# nRF52832_extend.net
KiCad netlist of a schematic drawn in Altium Designer
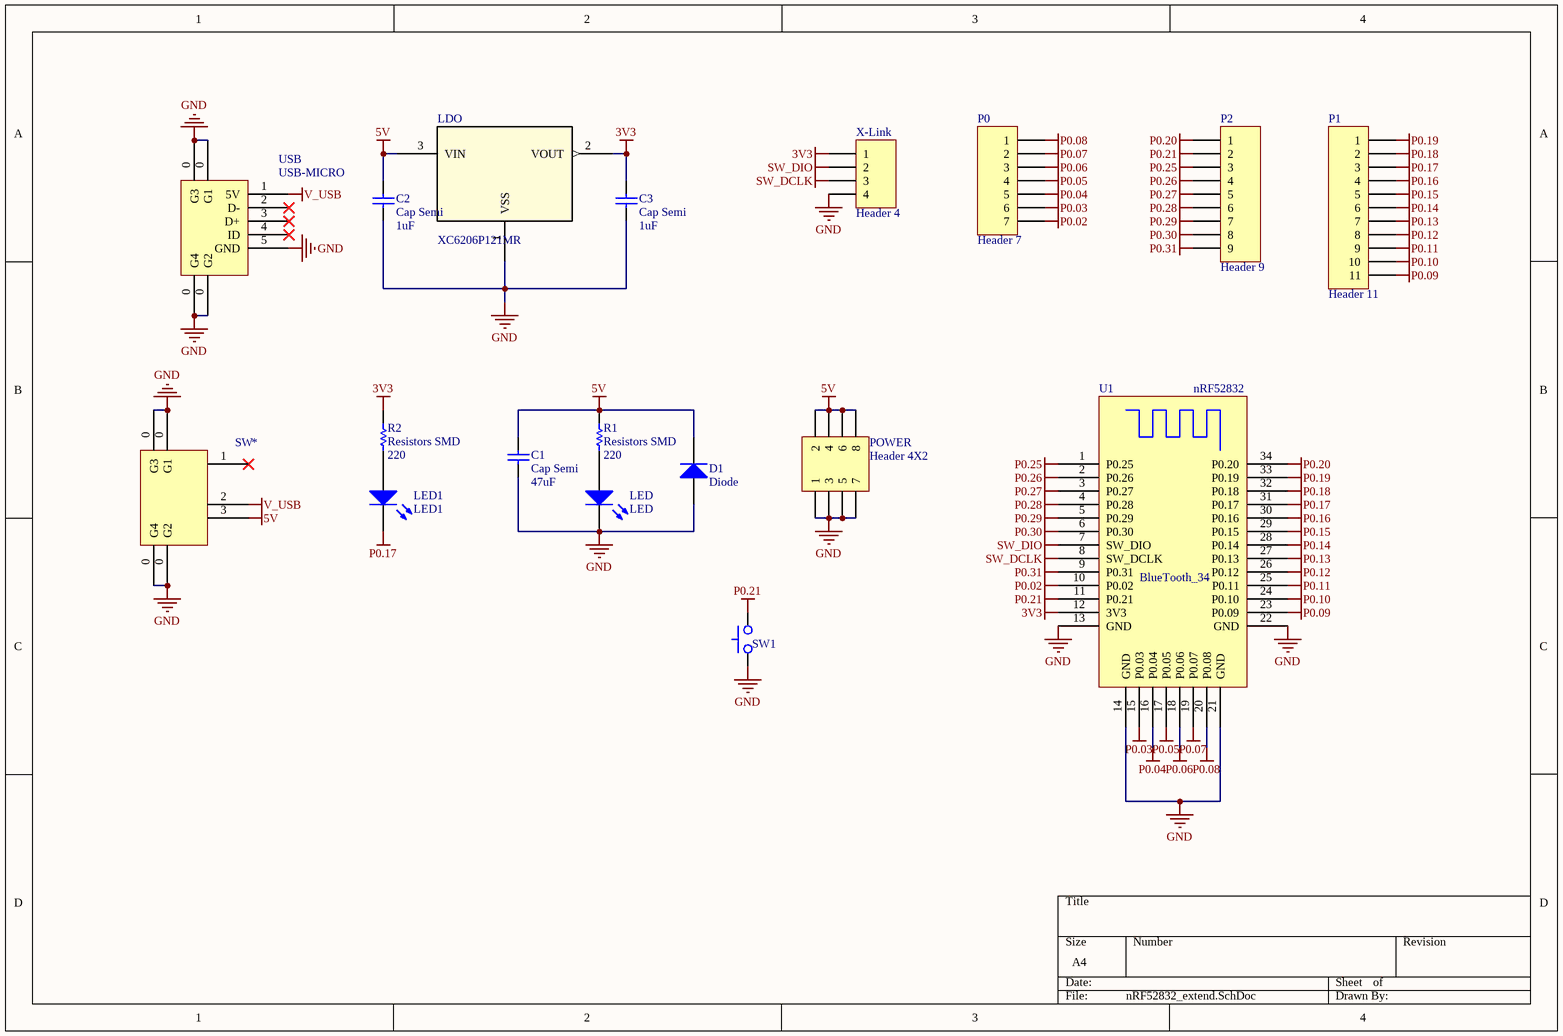
[diagram p0: nRF52832_extend.SchDoc]

(export (version "E")
  (design (tool "Eeschema 10.0.6"))
  (components
    (comp (ref "*") (value "SW") (footprint "SW_mk12c02") (libsource (lib "Mylibrary") (part "SW_mk12c02")))
    (comp (ref "C1")
      (value "Cap Semi")
      (footprint "C0805")
      (description "Capacitor (Semiconductor SIM Model)")
      (fields (field (name "ALTIUM_VALUE") "47uF") (field (name "PUBLISHER") "Altium Limited"))
      (libsource (lib "Mylibrary") (part "Cap Semi"))
    )
    (comp (ref "C2")
      (value "Cap Semi")
      (footprint "C0805")
      (description "Capacitor (Semiconductor SIM Model)")
      (fields (field (name "ALTIUM_VALUE") "1uF") (field (name "PUBLISHER") "Altium Limited"))
      (libsource (lib "Mylibrary") (part "Cap Semi"))
    )
    (comp (ref "C3")
      (value "Cap Semi")
      (footprint "C0805")
      (description "Capacitor (Semiconductor SIM Model)")
      (fields (field (name "ALTIUM_VALUE") "1uF") (field (name "PUBLISHER") "Altium Limited"))
      (libsource (lib "Mylibrary") (part "Cap Semi"))
    )
    (comp (ref "D1")
      (value "Diode")
      (footprint "6-0805_M")
      (description "Default Diode")
      (fields (field (name "PUBLISHER") "Altium Limited"))
      (libsource (lib "Miscellaneous Devices") (part "Diode"))
    )
    (comp (ref "LDO")
      (value "XC6206P121MR")
      (footprint "SOT-23")
      (description "Imported")
      (libsource (lib "Mylibrary") (part "XC6206P121MR"))
    )
    (comp (ref "LED")
      (value "LED")
      (footprint "0805 2.0X1.25X1.1")
      (description "Typical INFRARED GaAs LED")
      (fields (field (name "PUBLISHER") "Altium Limited"))
      (libsource (lib "Mylibrary") (part "LED"))
    )
    (comp (ref "LED1")
      (value "LED1")
      (footprint "0805 2.0X1.25X1.1")
      (description "Typical INFRARED GaAs LED")
      (fields (field (name "PUBLISHER") "Altium Limited"))
      (libsource (lib "Mylibrary") (part "LED"))
    )
    (comp (ref "P0")
      (value "Header 7")
      (footprint "HDR1X7")
      (description "Header, 7-Pin")
      (fields (field (name "PUBLISHER") "Altium Limited"))
      (libsource (lib "Miscellaneous Connectors") (part "Header 7"))
    )
    (comp (ref "P1")
      (value "Header 11")
      (footprint "HDR1X11")
      (description "Header, 11-Pin")
      (fields (field (name "PUBLISHER") "Altium Limited"))
      (libsource (lib "Miscellaneous Connectors") (part "Header 11"))
    )
    (comp (ref "P2")
      (value "Header 9")
      (footprint "HDR1X9")
      (description "Header, 9-Pin")
      (fields (field (name "PUBLISHER") "Altium Limited"))
      (libsource (lib "Miscellaneous Connectors") (part "Header 9"))
    )
    (comp (ref "POWER")
      (value "Header 4X2")
      (footprint "HDR2X4")
      (description "Header, 4-Pin, Dual row")
      (fields (field (name "PUBLISHER") "Altium Limited"))
      (libsource (lib "Miscellaneous Connectors") (part "Header 4X2"))
    )
    (comp (ref "R1")
      (value "Resistors SMD")
      (footprint "6-0805_M")
      (description "Resistor")
      (fields (field (name "ALTIUM_VALUE") "220"))
      (libsource (lib "Mylibrary") (part "Resistors SMD"))
    )
    (comp (ref "R2")
      (value "Resistors SMD")
      (footprint "6-0805_M")
      (description "Resistor")
      (fields (field (name "ALTIUM_VALUE") "220"))
      (libsource (lib "Mylibrary") (part "Resistors SMD"))
    )
    (comp (ref "SW1")
      (value "SW-PB")
      (footprint "SWITCH_SMD_6x3.5")
      (description "按鈕開關")
      (fields (field (name "PUBLISHER") "Altium Limited"))
      (libsource (lib "NTUST_nRF51_TAG") (part "SW-PB"))
    )
    (comp (ref "U1")
      (value "nRF52832")
      (footprint "BlueTooth_34_SMD")
      (libsource (lib "Mylibrary") (part "nRF52832"))
    )
    (comp (ref "USB")
      (value "USB-MICRO")
      (footprint "USB-MICRO")
      (libsource (lib "Mylibrary") (part "USB-MICRO"))
    )
    (comp (ref "X-Link")
      (value "Header 4")
      (footprint "HDR1X4")
      (description "Header, 4-Pin")
      (fields (field (name "PUBLISHER") "Altium Limited"))
      (libsource (lib "Miscellaneous Connectors") (part "Header 4"))
    )
  )
  (nets
    (net (code "1") (name "3V3") (class "Default")
      (node (ref "C3") (pin "2") (pinfunction "2_2") (pintype "passive"))
      (node (ref "LDO") (pin "2") (pinfunction "VOUT_2") (pintype "output"))
      (node (ref "R2") (pin "2") (pinfunction "2_2") (pintype "passive"))
      (node (ref "U1") (pin "12") (pinfunction "3V3_12") (pintype "passive"))
      (node (ref "X-Link") (pin "1") (pinfunction "1_1") (pintype "passive"))
    )
    (net (code "2") (name "5V") (class "Default")
      (node (ref "*") (pin "3") (pintype "passive"))
      (node (ref "C1") (pin "2") (pinfunction "2_2") (pintype "passive"))
      (node (ref "C2") (pin "2") (pinfunction "2_2") (pintype "passive"))
      (node (ref "D1") (pin "2") (pinfunction "K_2") (pintype "passive"))
      (node (ref "LDO") (pin "3") (pinfunction "VIN_3") (pintype "power_in"))
      (node (ref "POWER") (pin "2") (pinfunction "2_2") (pintype "passive"))
      (node (ref "POWER") (pin "4") (pinfunction "4_4") (pintype "passive"))
      (node (ref "POWER") (pin "6") (pinfunction "6_6") (pintype "passive"))
      (node (ref "POWER") (pin "8") (pinfunction "8_8") (pintype "passive"))
      (node (ref "R1") (pin "2") (pinfunction "2_2") (pintype "passive"))
    )
    (net (code "3") (name "GND") (class "Default")
      (node (ref "*") (pin "0") (pinfunction "G2_0") (pintype "power_in"))
      (node (ref "C1") (pin "1") (pinfunction "1_1") (pintype "passive"))
      (node (ref "C2") (pin "1") (pinfunction "1_1") (pintype "passive"))
      (node (ref "C3") (pin "1") (pinfunction "1_1") (pintype "passive"))
      (node (ref "D1") (pin "1") (pinfunction "A_1") (pintype "passive"))
      (node (ref "LDO") (pin "1") (pinfunction "VSS_1") (pintype "passive"))
      (node (ref "LED") (pin "2") (pinfunction "K_2") (pintype "passive"))
      (node (ref "POWER") (pin "1") (pinfunction "1_1") (pintype "passive"))
      (node (ref "POWER") (pin "3") (pinfunction "3_3") (pintype "passive"))
      (node (ref "POWER") (pin "5") (pinfunction "5_5") (pintype "passive"))
      (node (ref "POWER") (pin "7") (pinfunction "7_7") (pintype "passive"))
      (node (ref "SW1") (pin "2") (pinfunction "2_2") (pintype "passive"))
      (node (ref "U1") (pin "13") (pinfunction "GND_13") (pintype "passive"))
      (node (ref "U1") (pin "14") (pinfunction "GND_14") (pintype "passive"))
      (node (ref "U1") (pin "21") (pinfunction "GND_21") (pintype "passive"))
      (node (ref "U1") (pin "22") (pinfunction "GND_22") (pintype "passive"))
      (node (ref "USB") (pin "0") (pinfunction "G1_0") (pintype "power_in"))
      (node (ref "USB") (pin "5") (pinfunction "GND_5") (pintype "passive"))
      (node (ref "X-Link") (pin "4") (pinfunction "4_4") (pintype "passive"))
    )
    (net (code "4") (name "Net-(LED-A)") (class "Default")
      (node (ref "LED") (pin "1") (pinfunction "A_1") (pintype "passive"))
      (node (ref "R1") (pin "1") (pinfunction "1_1") (pintype "passive"))
    )
    (net (code "5") (name "Net-(LED1-A)") (class "Default")
      (node (ref "LED1") (pin "1") (pinfunction "A_1") (pintype "passive"))
      (node (ref "R2") (pin "1") (pinfunction "1_1") (pintype "passive"))
    )
    (net (code "6") (name "P0.02") (class "Default")
      (node (ref "P0") (pin "7") (pinfunction "7_7") (pintype "passive"))
      (node (ref "U1") (pin "10") (pinfunction "P0.02_10") (pintype "passive"))
    )
    (net (code "7") (name "P0.03") (class "Default")
      (node (ref "P0") (pin "6") (pinfunction "6_6") (pintype "passive"))
      (node (ref "U1") (pin "15") (pinfunction "P0.03_15") (pintype "passive"))
    )
    (net (code "8") (name "P0.04") (class "Default")
      (node (ref "P0") (pin "5") (pinfunction "5_5") (pintype "passive"))
      (node (ref "U1") (pin "16") (pinfunction "P0.04_16") (pintype "passive"))
    )
    (net (code "9") (name "P0.05") (class "Default")
      (node (ref "P0") (pin "4") (pinfunction "4_4") (pintype "passive"))
      (node (ref "U1") (pin "17") (pinfunction "P0.05_17") (pintype "passive"))
    )
    (net (code "10") (name "P0.06") (class "Default")
      (node (ref "P0") (pin "3") (pinfunction "3_3") (pintype "passive"))
      (node (ref "U1") (pin "18") (pinfunction "P0.06_18") (pintype "passive"))
    )
    (net (code "11") (name "P0.07") (class "Default")
      (node (ref "P0") (pin "2") (pinfunction "2_2") (pintype "passive"))
      (node (ref "U1") (pin "19") (pinfunction "P0.07_19") (pintype "passive"))
    )
    (net (code "12") (name "P0.08") (class "Default")
      (node (ref "P0") (pin "1") (pinfunction "1_1") (pintype "passive"))
      (node (ref "U1") (pin "20") (pinfunction "P0.08_20") (pintype "passive"))
    )
    (net (code "13") (name "P0.09") (class "Default")
      (node (ref "P1") (pin "11") (pinfunction "11_11") (pintype "passive"))
      (node (ref "U1") (pin "23") (pinfunction "P0.09_23") (pintype "passive"))
    )
    (net (code "14") (name "P0.10") (class "Default")
      (node (ref "P1") (pin "10") (pinfunction "10_10") (pintype "passive"))
      (node (ref "U1") (pin "24") (pinfunction "P0.10_24") (pintype "passive"))
    )
    (net (code "15") (name "P0.11") (class "Default")
      (node (ref "P1") (pin "9") (pinfunction "9_9") (pintype "passive"))
      (node (ref "U1") (pin "25") (pinfunction "P0.11_25") (pintype "passive"))
    )
    (net (code "16") (name "P0.12") (class "Default")
      (node (ref "P1") (pin "8") (pinfunction "8_8") (pintype "passive"))
      (node (ref "U1") (pin "26") (pinfunction "P0.12_26") (pintype "passive"))
    )
    (net (code "17") (name "P0.13") (class "Default")
      (node (ref "P1") (pin "7") (pinfunction "7_7") (pintype "passive"))
      (node (ref "U1") (pin "27") (pinfunction "P0.13_27") (pintype "passive"))
    )
    (net (code "18") (name "P0.14") (class "Default")
      (node (ref "P1") (pin "6") (pinfunction "6_6") (pintype "passive"))
      (node (ref "U1") (pin "28") (pinfunction "P0.14_28") (pintype "passive"))
    )
    (net (code "19") (name "P0.15") (class "Default")
      (node (ref "P1") (pin "5") (pinfunction "5_5") (pintype "passive"))
      (node (ref "U1") (pin "29") (pinfunction "P0.15_29") (pintype "passive"))
    )
    (net (code "20") (name "P0.16") (class "Default")
      (node (ref "P1") (pin "4") (pinfunction "4_4") (pintype "passive"))
      (node (ref "U1") (pin "30") (pinfunction "P0.16_30") (pintype "passive"))
    )
    (net (code "21") (name "P0.17") (class "Default")
      (node (ref "LED1") (pin "2") (pinfunction "K_2") (pintype "passive"))
      (node (ref "P1") (pin "3") (pinfunction "3_3") (pintype "passive"))
      (node (ref "U1") (pin "31") (pinfunction "P0.17_31") (pintype "passive"))
    )
    (net (code "22") (name "P0.18") (class "Default")
      (node (ref "P1") (pin "2") (pinfunction "2_2") (pintype "passive"))
      (node (ref "U1") (pin "32") (pinfunction "P0.18_32") (pintype "passive"))
    )
    (net (code "23") (name "P0.19") (class "Default")
      (node (ref "P1") (pin "1") (pinfunction "1_1") (pintype "passive"))
      (node (ref "U1") (pin "33") (pinfunction "P0.19_33") (pintype "passive"))
    )
    (net (code "24") (name "P0.20") (class "Default")
      (node (ref "P2") (pin "1") (pinfunction "1_1") (pintype "passive"))
      (node (ref "U1") (pin "34") (pinfunction "P0.20_34") (pintype "passive"))
    )
    (net (code "25") (name "P0.21") (class "Default")
      (node (ref "P2") (pin "2") (pinfunction "2_2") (pintype "passive"))
      (node (ref "SW1") (pin "1") (pinfunction "1_1") (pintype "passive"))
      (node (ref "U1") (pin "11") (pinfunction "P0.21_11") (pintype "passive"))
    )
    (net (code "26") (name "P0.25") (class "Default")
      (node (ref "P2") (pin "3") (pinfunction "3_3") (pintype "passive"))
      (node (ref "U1") (pin "1") (pinfunction "P0.25_1") (pintype "passive"))
    )
    (net (code "27") (name "P0.26") (class "Default")
      (node (ref "P2") (pin "4") (pinfunction "4_4") (pintype "passive"))
      (node (ref "U1") (pin "2") (pinfunction "P0.26_2") (pintype "passive"))
    )
    (net (code "28") (name "P0.27") (class "Default")
      (node (ref "P2") (pin "5") (pinfunction "5_5") (pintype "passive"))
      (node (ref "U1") (pin "3") (pinfunction "P0.27_3") (pintype "passive"))
    )
    (net (code "29") (name "P0.28") (class "Default")
      (node (ref "P2") (pin "6") (pinfunction "6_6") (pintype "passive"))
      (node (ref "U1") (pin "4") (pinfunction "P0.28_4") (pintype "passive"))
    )
    (net (code "30") (name "P0.29") (class "Default")
      (node (ref "P2") (pin "7") (pinfunction "7_7") (pintype "passive"))
      (node (ref "U1") (pin "5") (pinfunction "P0.29_5") (pintype "passive"))
    )
    (net (code "31") (name "P0.30") (class "Default")
      (node (ref "P2") (pin "8") (pinfunction "8_8") (pintype "passive"))
      (node (ref "U1") (pin "6") (pinfunction "P0.30_6") (pintype "passive"))
    )
    (net (code "32") (name "P0.31") (class "Default")
      (node (ref "P2") (pin "9") (pinfunction "9_9") (pintype "passive"))
      (node (ref "U1") (pin "9") (pinfunction "P0.31_9") (pintype "passive"))
    )
    (net (code "33") (name "SW_DCLK") (class "Default")
      (node (ref "U1") (pin "8") (pinfunction "SW_DCLK_8") (pintype "passive"))
      (node (ref "X-Link") (pin "3") (pinfunction "3_3") (pintype "passive"))
    )
    (net (code "34") (name "SW_DIO") (class "Default")
      (node (ref "U1") (pin "7") (pinfunction "SW_DIO_7") (pintype "passive"))
      (node (ref "X-Link") (pin "2") (pinfunction "2_2") (pintype "passive"))
    )
    (net (code "35") (name "V_USB") (class "Default")
      (node (ref "*") (pin "2") (pintype "passive"))
      (node (ref "USB") (pin "1") (pinfunction "5V_1") (pintype "passive"))
    )
    (net (code "36") (name "unconnected-(*-Pad1)") (class "Default")
      (node (ref "*") (pin "1") (pintype "passive+no_connect"))
    )
    (net (code "37") (name "unconnected-(USB-D+-Pad3)") (class "Default")
      (node (ref "USB") (pin "3") (pinfunction "D+_3") (pintype "passive+no_connect"))
    )
    (net (code "38") (name "unconnected-(USB-D--Pad2)") (class "Default")
      (node (ref "USB") (pin "2") (pinfunction "D-_2") (pintype "passive+no_connect"))
    )
    (net (code "39") (name "unconnected-(USB-ID-Pad4)") (class "Default")
      (node (ref "USB") (pin "4") (pinfunction "ID_4") (pintype "passive+no_connect"))
    )
  )
)
